# redLED12Vfive.net
KiCad netlist of a schematic drawn in EAGLE
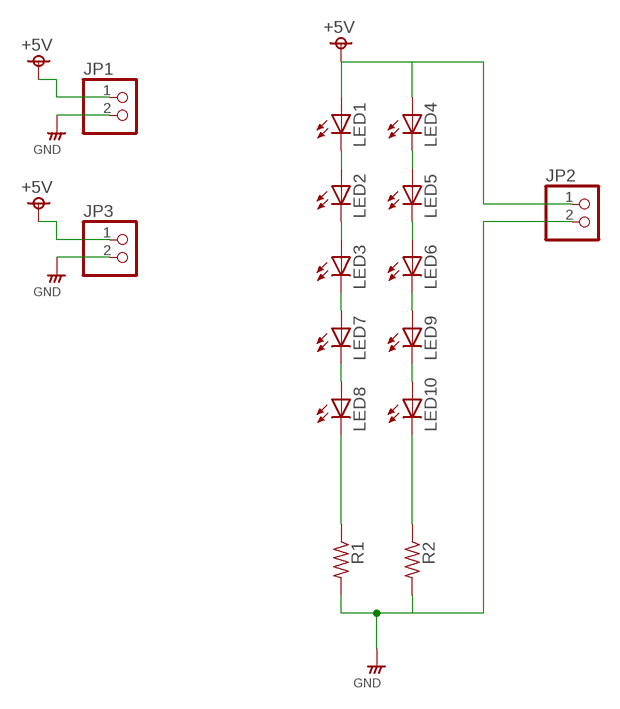
[diagram p0: schematic, sheet 1]

(export (version "E")
  (design (tool "Eeschema 10.0.6"))
  (components
    (comp (ref "JP1")
      (value "PINHD-1X2\"")
      (footprint "eagle-import:1_02")
      (libsource (lib "eagle-import") (part "PINHD-1X2{dblquote}"))
    )
    (comp (ref "JP2")
      (value "PINHD-1X2\"")
      (footprint "eagle-import:1_02")
      (libsource (lib "eagle-import") (part "PINHD-1X2{dblquote}"))
    )
    (comp (ref "JP3")
      (value "PINHD-1X2\"")
      (footprint "eagle-import:1_02")
      (libsource (lib "eagle-import") (part "PINHD-1X2{dblquote}"))
    )
    (comp (ref "LED1")
      (value "LED5MM")
      (footprint "eagle-import:LED5MM")
      (libsource (lib "eagle-import") (part "LED5MM"))
    )
    (comp (ref "LED2")
      (value "LED5MM")
      (footprint "eagle-import:LED5MM")
      (libsource (lib "eagle-import") (part "LED5MM"))
    )
    (comp (ref "LED3")
      (value "LED5MM")
      (footprint "eagle-import:LED5MM")
      (libsource (lib "eagle-import") (part "LED5MM"))
    )
    (comp (ref "LED4")
      (value "LED5MM")
      (footprint "eagle-import:LED5MM")
      (libsource (lib "eagle-import") (part "LED5MM"))
    )
    (comp (ref "LED5")
      (value "LED5MM")
      (footprint "eagle-import:LED5MM")
      (libsource (lib "eagle-import") (part "LED5MM"))
    )
    (comp (ref "LED6")
      (value "LED5MM")
      (footprint "eagle-import:LED5MM")
      (libsource (lib "eagle-import") (part "LED5MM"))
    )
    (comp (ref "LED7")
      (value "LED5MM")
      (footprint "eagle-import:LED5MM")
      (libsource (lib "eagle-import") (part "LED5MM"))
    )
    (comp (ref "LED8")
      (value "LED5MM")
      (footprint "eagle-import:LED5MM")
      (libsource (lib "eagle-import") (part "LED5MM"))
    )
    (comp (ref "LED9")
      (value "LED5MM")
      (footprint "eagle-import:LED5MM")
      (libsource (lib "eagle-import") (part "LED5MM"))
    )
    (comp (ref "LED10")
      (value "LED5MM")
      (footprint "eagle-import:LED5MM")
      (libsource (lib "eagle-import") (part "LED5MM"))
    )
    (comp (ref "R1")
      (value "RESISTORS-3")
      (footprint "eagle-import:R_0.2")
      (libsource (lib "eagle-import") (part "RESISTORS-3"))
    )
    (comp (ref "R2")
      (value "RESISTORS-3")
      (footprint "eagle-import:R_0.2")
      (libsource (lib "eagle-import") (part "RESISTORS-3"))
    )
  )
  (nets
    (net (code "1") (name "/+5V") (class "Default")
      (node (ref "JP1") (pin "1") (pinfunction "1_1") (pintype "passive"))
      (node (ref "JP2") (pin "1") (pinfunction "1_1") (pintype "passive"))
      (node (ref "JP3") (pin "1") (pinfunction "1_1") (pintype "passive"))
      (node (ref "LED1") (pin "A") (pinfunction "A_A") (pintype "passive"))
      (node (ref "LED4") (pin "A") (pinfunction "A_A") (pintype "passive"))
    )
    (net (code "2") (name "GND") (class "Default")
      (node (ref "JP1") (pin "2") (pinfunction "2_2") (pintype "passive"))
      (node (ref "JP2") (pin "2") (pinfunction "2_2") (pintype "passive"))
      (node (ref "JP3") (pin "2") (pinfunction "2_2") (pintype "passive"))
      (node (ref "R1") (pin "2") (pinfunction "2_2") (pintype "passive"))
      (node (ref "R2") (pin "2") (pinfunction "2_2") (pintype "passive"))
    )
    (net (code "3") (name "Net-(LED1-C)") (class "Default")
      (node (ref "LED1") (pin "K") (pinfunction "C_K") (pintype "passive"))
      (node (ref "LED2") (pin "A") (pinfunction "A_A") (pintype "passive"))
    )
    (net (code "4") (name "Net-(LED2-C)") (class "Default")
      (node (ref "LED2") (pin "K") (pinfunction "C_K") (pintype "passive"))
      (node (ref "LED3") (pin "A") (pinfunction "A_A") (pintype "passive"))
    )
    (net (code "5") (name "Net-(LED3-C)") (class "Default")
      (node (ref "LED3") (pin "K") (pinfunction "C_K") (pintype "passive"))
      (node (ref "LED7") (pin "A") (pinfunction "A_A") (pintype "passive"))
    )
    (net (code "6") (name "Net-(LED4-C)") (class "Default")
      (node (ref "LED4") (pin "K") (pinfunction "C_K") (pintype "passive"))
      (node (ref "LED5") (pin "A") (pinfunction "A_A") (pintype "passive"))
    )
    (net (code "7") (name "Net-(LED5-C)") (class "Default")
      (node (ref "LED5") (pin "K") (pinfunction "C_K") (pintype "passive"))
      (node (ref "LED6") (pin "A") (pinfunction "A_A") (pintype "passive"))
    )
    (net (code "8") (name "Net-(LED6-C)") (class "Default")
      (node (ref "LED6") (pin "K") (pinfunction "C_K") (pintype "passive"))
      (node (ref "LED9") (pin "A") (pinfunction "A_A") (pintype "passive"))
    )
    (net (code "9") (name "Net-(LED7-C)") (class "Default")
      (node (ref "LED7") (pin "K") (pinfunction "C_K") (pintype "passive"))
      (node (ref "LED8") (pin "A") (pinfunction "A_A") (pintype "passive"))
    )
    (net (code "10") (name "Net-(LED8-C)") (class "Default")
      (node (ref "LED8") (pin "K") (pinfunction "C_K") (pintype "passive"))
      (node (ref "R1") (pin "1") (pinfunction "1_1") (pintype "passive"))
    )
    (net (code "11") (name "Net-(LED9-C)") (class "Default")
      (node (ref "LED10") (pin "A") (pinfunction "A_A") (pintype "passive"))
      (node (ref "LED9") (pin "K") (pinfunction "C_K") (pintype "passive"))
    )
    (net (code "12") (name "Net-(LED10-C)") (class "Default")
      (node (ref "LED10") (pin "K") (pinfunction "C_K") (pintype "passive"))
      (node (ref "R2") (pin "1") (pinfunction "1_1") (pintype "passive"))
    )
  )
)
